# MCU_power.net
KiCad netlist of a schematic drawn in Altium Designer
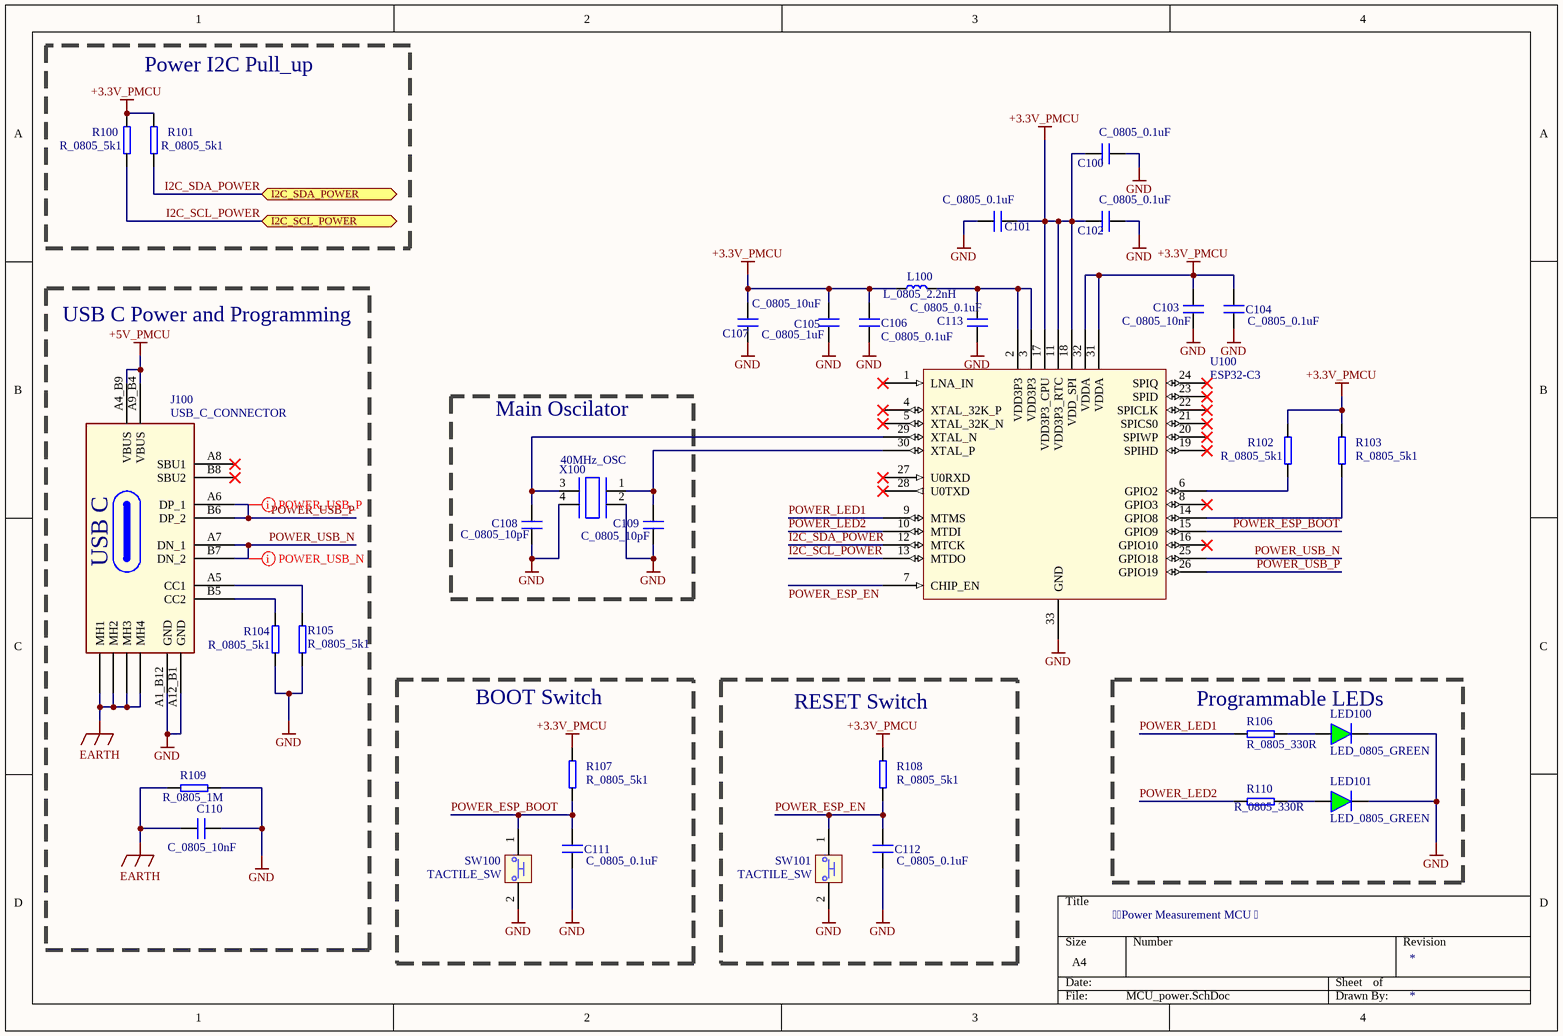
[diagram p0: MCU_power.SchDoc]

(export (version "E")
  (design (tool "Eeschema 10.0.6"))
  (components
    (comp (ref "C100")
      (value "C_0805_0.1uF")
      (footprint "CAP_0805")
      (fields (field (name "JLC PART NUMBER") "C28233"))
      (libsource (lib "Petar B") (part "0.1uF 0805"))
    )
    (comp (ref "C101")
      (value "C_0805_0.1uF")
      (footprint "CAP_0805")
      (fields (field (name "JLC PART NUMBER") "C28233"))
      (libsource (lib "Petar B") (part "0.1uF 0805"))
    )
    (comp (ref "C102")
      (value "C_0805_0.1uF")
      (footprint "CAP_0805")
      (fields (field (name "JLC PART NUMBER") "C28233"))
      (libsource (lib "Petar B") (part "0.1uF 0805"))
    )
    (comp (ref "C103")
      (value "C_0805_10nF")
      (footprint "CAP_0805")
      (fields (field (name "JLC PART NUMBER") "C1710"))
      (libsource (lib "Petar B") (part "0.1uF 0805"))
    )
    (comp (ref "C104")
      (value "C_0805_0.1uF")
      (footprint "CAP_0805")
      (fields (field (name "JLC PART NUMBER") "C28233"))
      (libsource (lib "Petar B") (part "0.1uF 0805"))
    )
    (comp (ref "C105")
      (value "C_0805_1uF")
      (footprint "CAP_0805")
      (fields (field (name "JLC PART NUMBER") "C28323"))
      (libsource (lib "Petar B") (part "1uF 0805"))
    )
    (comp (ref "C106")
      (value "C_0805_0.1uF")
      (footprint "CAP_0805")
      (fields (field (name "JLC PART NUMBER") "C28233"))
      (libsource (lib "Petar B") (part "0.1uF 0805"))
    )
    (comp (ref "C107")
      (value "C_0805_10uF")
      (footprint "CAP_0805")
      (fields (field (name "JLC PART NUMBER") "C15850"))
      (libsource (lib "Petar B") (part "10uF 0805"))
    )
    (comp (ref "C108")
      (value "C_0805_10pF")
      (footprint "CAP_0805")
      (fields (field (name "JLC PART NUMBER") "C107107"))
      (libsource (lib "Petar B") (part "0.1uF 0805"))
    )
    (comp (ref "C109")
      (value "C_0805_10pF")
      (footprint "CAP_0805")
      (fields (field (name "JLC PART NUMBER") "C107107"))
      (libsource (lib "Petar B") (part "0.1uF 0805"))
    )
    (comp (ref "C110")
      (value "C_0805_10nF")
      (footprint "CAP_0805")
      (fields (field (name "JLC PART NUMBER") "C1710"))
      (libsource (lib "Petar B") (part "0.1uF 0805"))
    )
    (comp (ref "C111")
      (value "C_0805_0.1uF")
      (footprint "CAP_0805")
      (fields (field (name "JLC PART NUMBER") "C28233"))
      (libsource (lib "Petar B") (part "0.1uF 0805"))
    )
    (comp (ref "C112")
      (value "C_0805_0.1uF")
      (footprint "CAP_0805")
      (fields (field (name "JLC PART NUMBER") "C28233"))
      (libsource (lib "Petar B") (part "0.1uF 0805"))
    )
    (comp (ref "C113")
      (value "C_0805_0.1uF")
      (footprint "CAP_0805")
      (fields (field (name "JLC PART NUMBER") "C28233"))
      (libsource (lib "Petar B") (part "0.1uF 0805"))
    )
    (comp (ref "J100")
      (value "USB_C_CONNECTOR")
      (footprint "USB_C_CONNECTOR-Footprint-1")
      (description "USB2.0, Type C, Top Mount, Ch 1.68MM, Dual Row SMT / Tap/rl")
      (fields (field (name "JLC PART NUMBER") "C2831450"))
      (libsource (lib "Petar B") (part "conn_usb_c"))
    )
    (comp (ref "L100")
      (value "L_0805_2.2nH")
      (footprint "L_0805")
      (description "Required a minimum current of 500mA and a resonant frequrency of at least 6GHz")
      (fields (field (name "JLC PART NUMBER") "C964055"))
      (libsource (lib "Petar B") (part "0805 2.2uH"))
    )
    (comp (ref "LED100")
      (value "LED_0805_GREEN")
      (footprint "LED_0806")
      (description "LED, Green, SMD, 0805 [2012 Metric], 30 mA, 2 V, 570 nm")
      (fields (field (name "JLC PART NUMBER") "C2297"))
      (libsource (lib "Petar B") (part "LED_GREEN"))
    )
    (comp (ref "LED101")
      (value "LED_0805_GREEN")
      (footprint "LED_0806")
      (description "LED, Green, SMD, 0805 [2012 Metric], 30 mA, 2 V, 570 nm")
      (fields (field (name "JLC PART NUMBER") "C2297"))
      (libsource (lib "Petar B") (part "LED_GREEN"))
    )
    (comp (ref "R100")
      (value "R_0805_5k1")
      (footprint "0805_RES")
      (fields (field (name "JLC PART NUMBER") "C27834"))
      (libsource (lib "Petar B") (part "4.7k0805"))
    )
    (comp (ref "R101")
      (value "R_0805_5k1")
      (footprint "0805_RES")
      (fields (field (name "JLC PART NUMBER") "C27834"))
      (libsource (lib "Petar B") (part "4.7k0805"))
    )
    (comp (ref "R102")
      (value "R_0805_5k1")
      (footprint "0805_RES")
      (fields (field (name "JLC PART NUMBER") "C27834"))
      (libsource (lib "Petar B") (part "4.7k0805"))
    )
    (comp (ref "R103")
      (value "R_0805_5k1")
      (footprint "0805_RES")
      (fields (field (name "JLC PART NUMBER") "C27834"))
      (libsource (lib "Petar B") (part "4.7k0805"))
    )
    (comp (ref "R104")
      (value "R_0805_5k1")
      (footprint "0805_RES")
      (fields (field (name "JLC PART NUMBER") "C27834"))
      (libsource (lib "Petar B") (part "4.7k0805"))
    )
    (comp (ref "R105")
      (value "R_0805_5k1")
      (footprint "0805_RES")
      (fields (field (name "JLC PART NUMBER") "C27834"))
      (libsource (lib "Petar B") (part "4.7k0805"))
    )
    (comp (ref "R106")
      (value "R_0805_330R")
      (footprint "0805_RES")
      (fields (field (name "JLC PART NUMBER") "C17630"))
      (libsource (lib "Petar B") (part "4.7k0805"))
    )
    (comp (ref "R107")
      (value "R_0805_5k1")
      (footprint "0805_RES")
      (fields (field (name "JLC PART NUMBER") "C27834"))
      (libsource (lib "Petar B") (part "4.7k0805"))
    )
    (comp (ref "R108")
      (value "R_0805_5k1")
      (footprint "0805_RES")
      (fields (field (name "JLC PART NUMBER") "C27834"))
      (libsource (lib "Petar B") (part "4.7k0805"))
    )
    (comp (ref "R109")
      (value "R_0805_1M")
      (footprint "0805_RES")
      (fields (field (name "JLC PART NUMBER") "C131391"))
      (libsource (lib "Petar B") (part "R_symbol"))
    )
    (comp (ref "R110")
      (value "R_0805_330R")
      (footprint "0805_RES")
      (fields (field (name "JLC PART NUMBER") "C17630"))
      (libsource (lib "Petar B") (part "4.7k0805"))
    )
    (comp (ref "SW100")
      (value "TACTILE_SW")
      (footprint "TACTILE_SW-Footprint-1")
      (fields (field (name "JLC PART NUMBER") "C455280"))
      (libsource (lib "Petar B") (part "TACTILE_SW"))
    )
    (comp (ref "SW101")
      (value "TACTILE_SW")
      (footprint "TACTILE_SW-Footprint-1")
      (fields (field (name "JLC PART NUMBER") "C455280"))
      (libsource (lib "Petar B") (part "TACTILE_SW"))
    )
    (comp (ref "U100")
      (value "ESP32-C3")
      (footprint "QFN127P600-8N")
      (description "33 pin ESP32_C3 Microcontroller")
      (fields (field (name "JLC PART NUMBER") "C2858491"))
      (libsource (lib "Petar B") (part "ESP32-C3_symbol"))
    )
    (comp (ref "X100")
      (value "40MHz_OSC")
      (footprint "40MHz_OSC-Footprint-1")
      (description "40 MHZ Oscillator, 10pF load capacitance")
      (fields (field (name "JLC PART NUMBER") "C426988"))
      (libsource (lib "Petar B") (part "OSC_SYMB"))
    )
  )
  (nets
    (net (code "1") (name "+3.3V_PMCU") (class "Default")
      (node (ref "C100") (pin "1") (pinfunction "1_1") (pintype "passive"))
      (node (ref "C101") (pin "2") (pinfunction "2_2") (pintype "passive"))
      (node (ref "C102") (pin "1") (pinfunction "1_1") (pintype "passive"))
      (node (ref "C103") (pin "2") (pinfunction "2_2") (pintype "passive"))
      (node (ref "C104") (pin "2") (pinfunction "2_2") (pintype "passive"))
      (node (ref "C105") (pin "2") (pinfunction "2_2") (pintype "passive"))
      (node (ref "C106") (pin "1") (pinfunction "1_1") (pintype "passive"))
      (node (ref "C107") (pin "2") (pinfunction "2_2") (pintype "passive"))
      (node (ref "L100") (pin "1") (pinfunction "1_1") (pintype "passive"))
      (node (ref "R100") (pin "1") (pinfunction "1_1") (pintype "passive"))
      (node (ref "R101") (pin "1") (pinfunction "1_1") (pintype "passive"))
      (node (ref "R102") (pin "1") (pinfunction "1_1") (pintype "passive"))
      (node (ref "R103") (pin "1") (pinfunction "1_1") (pintype "passive"))
      (node (ref "R107") (pin "1") (pinfunction "1_1") (pintype "passive"))
      (node (ref "R108") (pin "1") (pinfunction "1_1") (pintype "passive"))
      (node (ref "U100") (pin "11") (pinfunction "VDD3P3_RTC_11") (pintype "power_in"))
      (node (ref "U100") (pin "17") (pinfunction "VDD3P3_CPU_17") (pintype "power_in"))
      (node (ref "U100") (pin "18") (pinfunction "VDD_SPI_18") (pintype "power_in"))
      (node (ref "U100") (pin "31") (pinfunction "VDDA_31") (pintype "power_in"))
      (node (ref "U100") (pin "32") (pinfunction "VDDA_32") (pintype "power_in"))
    )
    (net (code "2") (name "+5V_PMCU") (class "Default")
      (node (ref "J100") (pin "A4_B9") (pinfunction "VBUS_A4_B9") (pintype "passive"))
      (node (ref "J100") (pin "A9_B4") (pinfunction "VBUS_A9_B4") (pintype "passive"))
    )
    (net (code "4") (name "/I2C_SCL_POWER") (class "Default")
      (node (ref "R100") (pin "2") (pinfunction "2_2") (pintype "passive"))
      (node (ref "U100") (pin "13") (pinfunction "MTDO_13") (pintype "bidirectional"))
    )
    (net (code "5") (name "/I2C_SDA_POWER") (class "Default")
      (node (ref "R101") (pin "2") (pinfunction "2_2") (pintype "passive"))
      (node (ref "U100") (pin "12") (pinfunction "MTCK_12") (pintype "bidirectional"))
    )
    (net (code "6") (name "/POWER_ESP_BOOT") (class "Default")
      (node (ref "C111") (pin "2") (pinfunction "2_2") (pintype "passive"))
      (node (ref "R107") (pin "2") (pinfunction "2_2") (pintype "passive"))
      (node (ref "SW100") (pin "1") (pinfunction "1_1") (pintype "passive"))
      (node (ref "U100") (pin "15") (pinfunction "GPIO9_15") (pintype "bidirectional"))
    )
    (net (code "7") (name "/POWER_ESP_EN") (class "Default")
      (node (ref "C112") (pin "2") (pinfunction "2_2") (pintype "passive"))
      (node (ref "R108") (pin "2") (pinfunction "2_2") (pintype "passive"))
      (node (ref "SW101") (pin "1") (pinfunction "1_1") (pintype "passive"))
      (node (ref "U100") (pin "7") (pinfunction "CHIP_EN_7") (pintype "input"))
    )
    (net (code "8") (name "/POWER_LED1") (class "Default")
      (node (ref "R106") (pin "2") (pinfunction "2_2") (pintype "passive"))
      (node (ref "U100") (pin "9") (pinfunction "MTMS_9") (pintype "bidirectional"))
    )
    (net (code "9") (name "/POWER_LED2") (class "Default")
      (node (ref "R110") (pin "2") (pinfunction "2_2") (pintype "passive"))
      (node (ref "U100") (pin "10") (pinfunction "MTDI_10") (pintype "bidirectional"))
    )
    (net (code "10") (name "/POWER_USB_N") (class "Default")
      (node (ref "J100") (pin "A7") (pinfunction "DN_1_A7") (pintype "passive"))
      (node (ref "J100") (pin "B7") (pinfunction "DN_2_B7") (pintype "passive"))
      (node (ref "U100") (pin "25") (pinfunction "GPIO18_25") (pintype "bidirectional"))
    )
    (net (code "11") (name "/POWER_USB_P") (class "Default")
      (node (ref "J100") (pin "A6") (pinfunction "DP_1_A6") (pintype "passive"))
      (node (ref "J100") (pin "B6") (pinfunction "DP_2_B6") (pintype "passive"))
      (node (ref "U100") (pin "26") (pinfunction "GPIO19_26") (pintype "bidirectional"))
    )
    (net (code "12") (name "EARTH") (class "Default")
      (node (ref "C110") (pin "1") (pinfunction "1_1") (pintype "passive"))
      (node (ref "J100") (pin "MH1") (pinfunction "MH1_MH1") (pintype "passive"))
      (node (ref "J100") (pin "MH2") (pinfunction "MH2_MH2") (pintype "passive"))
      (node (ref "J100") (pin "MH3") (pinfunction "MH3_MH3") (pintype "passive"))
      (node (ref "J100") (pin "MH4") (pinfunction "MH4_MH4") (pintype "passive"))
      (node (ref "R109") (pin "2") (pinfunction "2_2") (pintype "passive"))
    )
    (net (code "13") (name "GND") (class "Default")
      (node (ref "C100") (pin "2") (pinfunction "2_2") (pintype "passive"))
      (node (ref "C101") (pin "1") (pinfunction "1_1") (pintype "passive"))
      (node (ref "C102") (pin "2") (pinfunction "2_2") (pintype "passive"))
      (node (ref "C103") (pin "1") (pinfunction "1_1") (pintype "passive"))
      (node (ref "C104") (pin "1") (pinfunction "1_1") (pintype "passive"))
      (node (ref "C105") (pin "1") (pinfunction "1_1") (pintype "passive"))
      (node (ref "C106") (pin "2") (pinfunction "2_2") (pintype "passive"))
      (node (ref "C107") (pin "1") (pinfunction "1_1") (pintype "passive"))
      (node (ref "C108") (pin "1") (pinfunction "1_1") (pintype "passive"))
      (node (ref "C109") (pin "1") (pinfunction "1_1") (pintype "passive"))
      (node (ref "C110") (pin "2") (pinfunction "2_2") (pintype "passive"))
      (node (ref "C111") (pin "1") (pinfunction "1_1") (pintype "passive"))
      (node (ref "C112") (pin "1") (pinfunction "1_1") (pintype "passive"))
      (node (ref "C113") (pin "2") (pinfunction "2_2") (pintype "passive"))
      (node (ref "J100") (pin "A12_B1") (pinfunction "GND_A12_B1") (pintype "passive"))
      (node (ref "J100") (pin "A1_B12") (pinfunction "GND_A1_B12") (pintype "passive"))
      (node (ref "LED100") (pin "1") (pinfunction "1_1") (pintype "passive"))
      (node (ref "LED101") (pin "1") (pinfunction "1_1") (pintype "passive"))
      (node (ref "R104") (pin "2") (pinfunction "2_2") (pintype "passive"))
      (node (ref "R105") (pin "2") (pinfunction "2_2") (pintype "passive"))
      (node (ref "R109") (pin "1") (pinfunction "1_1") (pintype "passive"))
      (node (ref "SW100") (pin "2") (pinfunction "2_2") (pintype "passive"))
      (node (ref "SW101") (pin "2") (pinfunction "2_2") (pintype "passive"))
      (node (ref "U100") (pin "33") (pinfunction "GND_33") (pintype "power_in"))
      (node (ref "X100") (pin "2") (pinfunction "2_2") (pintype "passive"))
      (node (ref "X100") (pin "4") (pinfunction "4_4") (pintype "passive"))
    )
    (net (code "14") (name "Net-(C113-Pad1)") (class "Default")
      (node (ref "C113") (pin "1") (pinfunction "1_1") (pintype "passive"))
      (node (ref "L100") (pin "2") (pinfunction "2_2") (pintype "passive"))
      (node (ref "U100") (pin "2") (pinfunction "VDD3P3_2") (pintype "power_in"))
      (node (ref "U100") (pin "3") (pinfunction "VDD3P3_3") (pintype "power_in"))
    )
    (net (code "15") (name "Net-(J100-CC1)") (class "Default")
      (node (ref "J100") (pin "A5") (pinfunction "CC1_A5") (pintype "passive"))
      (node (ref "R105") (pin "1") (pinfunction "1_1") (pintype "passive"))
    )
    (net (code "16") (name "Net-(J100-CC2)") (class "Default")
      (node (ref "J100") (pin "B5") (pinfunction "CC2_B5") (pintype "passive"))
      (node (ref "R104") (pin "1") (pinfunction "1_1") (pintype "passive"))
    )
    (net (code "17") (name "Net-(LED100-Pad2)") (class "Default")
      (node (ref "LED100") (pin "2") (pinfunction "2_2") (pintype "passive"))
      (node (ref "R106") (pin "1") (pinfunction "1_1") (pintype "passive"))
    )
    (net (code "18") (name "Net-(LED101-Pad2)") (class "Default")
      (node (ref "LED101") (pin "2") (pinfunction "2_2") (pintype "passive"))
      (node (ref "R110") (pin "1") (pinfunction "1_1") (pintype "passive"))
    )
    (net (code "19") (name "Net-(U100-GPIO2)") (class "Default")
      (node (ref "R102") (pin "2") (pinfunction "2_2") (pintype "passive"))
      (node (ref "U100") (pin "6") (pinfunction "GPIO2_6") (pintype "bidirectional"))
    )
    (net (code "20") (name "Net-(U100-GPIO8)") (class "Default")
      (node (ref "R103") (pin "2") (pinfunction "2_2") (pintype "passive"))
      (node (ref "U100") (pin "14") (pinfunction "GPIO8_14") (pintype "bidirectional"))
    )
    (net (code "21") (name "Net-(U100-XTAL_N)") (class "Default")
      (node (ref "C108") (pin "2") (pinfunction "2_2") (pintype "passive"))
      (node (ref "U100") (pin "29") (pinfunction "XTAL_N_29") (pintype "bidirectional"))
      (node (ref "X100") (pin "3") (pinfunction "3_3") (pintype "passive"))
    )
    (net (code "22") (name "Net-(U100-XTAL_P)") (class "Default")
      (node (ref "C109") (pin "2") (pinfunction "2_2") (pintype "passive"))
      (node (ref "U100") (pin "30") (pinfunction "XTAL_P_30") (pintype "bidirectional"))
      (node (ref "X100") (pin "1") (pinfunction "1_1") (pintype "passive"))
    )
    (net (code "23") (name "unconnected-(J100-SBU1-PadA8)") (class "Default")
      (node (ref "J100") (pin "A8") (pinfunction "SBU1_A8") (pintype "passive+no_connect"))
    )
    (net (code "24") (name "unconnected-(J100-SBU2-PadB8)") (class "Default")
      (node (ref "J100") (pin "B8") (pinfunction "SBU2_B8") (pintype "passive+no_connect"))
    )
    (net (code "25") (name "unconnected-(U100-GPIO3-Pad8)") (class "Default")
      (node (ref "U100") (pin "8") (pinfunction "GPIO3_8") (pintype "bidirectional+no_connect"))
    )
    (net (code "26") (name "unconnected-(U100-GPIO10-Pad16)") (class "Default")
      (node (ref "U100") (pin "16") (pinfunction "GPIO10_16") (pintype "bidirectional+no_connect"))
    )
    (net (code "27") (name "unconnected-(U100-LNA_IN-Pad1)") (class "Default")
      (node (ref "U100") (pin "1") (pinfunction "LNA_IN_1") (pintype "input+no_connect"))
    )
    (net (code "28") (name "unconnected-(U100-SPICLK-Pad22)") (class "Default")
      (node (ref "U100") (pin "22") (pinfunction "SPICLK_22") (pintype "bidirectional+no_connect"))
    )
    (net (code "29") (name "unconnected-(U100-SPICS0-Pad21)") (class "Default")
      (node (ref "U100") (pin "21") (pinfunction "SPICS0_21") (pintype "bidirectional+no_connect"))
    )
    (net (code "30") (name "unconnected-(U100-SPID-Pad23)") (class "Default")
      (node (ref "U100") (pin "23") (pinfunction "SPID_23") (pintype "bidirectional+no_connect"))
    )
    (net (code "31") (name "unconnected-(U100-SPIHD-Pad19)") (class "Default")
      (node (ref "U100") (pin "19") (pinfunction "SPIHD_19") (pintype "bidirectional+no_connect"))
    )
    (net (code "32") (name "unconnected-(U100-SPIQ-Pad24)") (class "Default")
      (node (ref "U100") (pin "24") (pinfunction "SPIQ_24") (pintype "bidirectional+no_connect"))
    )
    (net (code "33") (name "unconnected-(U100-SPIWP-Pad20)") (class "Default")
      (node (ref "U100") (pin "20") (pinfunction "SPIWP_20") (pintype "bidirectional+no_connect"))
    )
    (net (code "34") (name "unconnected-(U100-U0RXD-Pad27)") (class "Default")
      (node (ref "U100") (pin "27") (pinfunction "U0RXD_27") (pintype "input+no_connect"))
    )
    (net (code "35") (name "unconnected-(U100-U0TXD-Pad28)") (class "Default")
      (node (ref "U100") (pin "28") (pinfunction "U0TXD_28") (pintype "output+no_connect"))
    )
    (net (code "36") (name "unconnected-(U100-XTAL_32K_N-Pad5)") (class "Default")
      (node (ref "U100") (pin "5") (pinfunction "XTAL_32K_N_5") (pintype "bidirectional+no_connect"))
    )
    (net (code "37") (name "unconnected-(U100-XTAL_32K_P-Pad4)") (class "Default")
      (node (ref "U100") (pin "4") (pinfunction "XTAL_32K_P_4") (pintype "bidirectional+no_connect"))
    )
  )
)
